# Retro_Programmer-v0_1.net
KiCad netlist of a schematic drawn in EAGLE
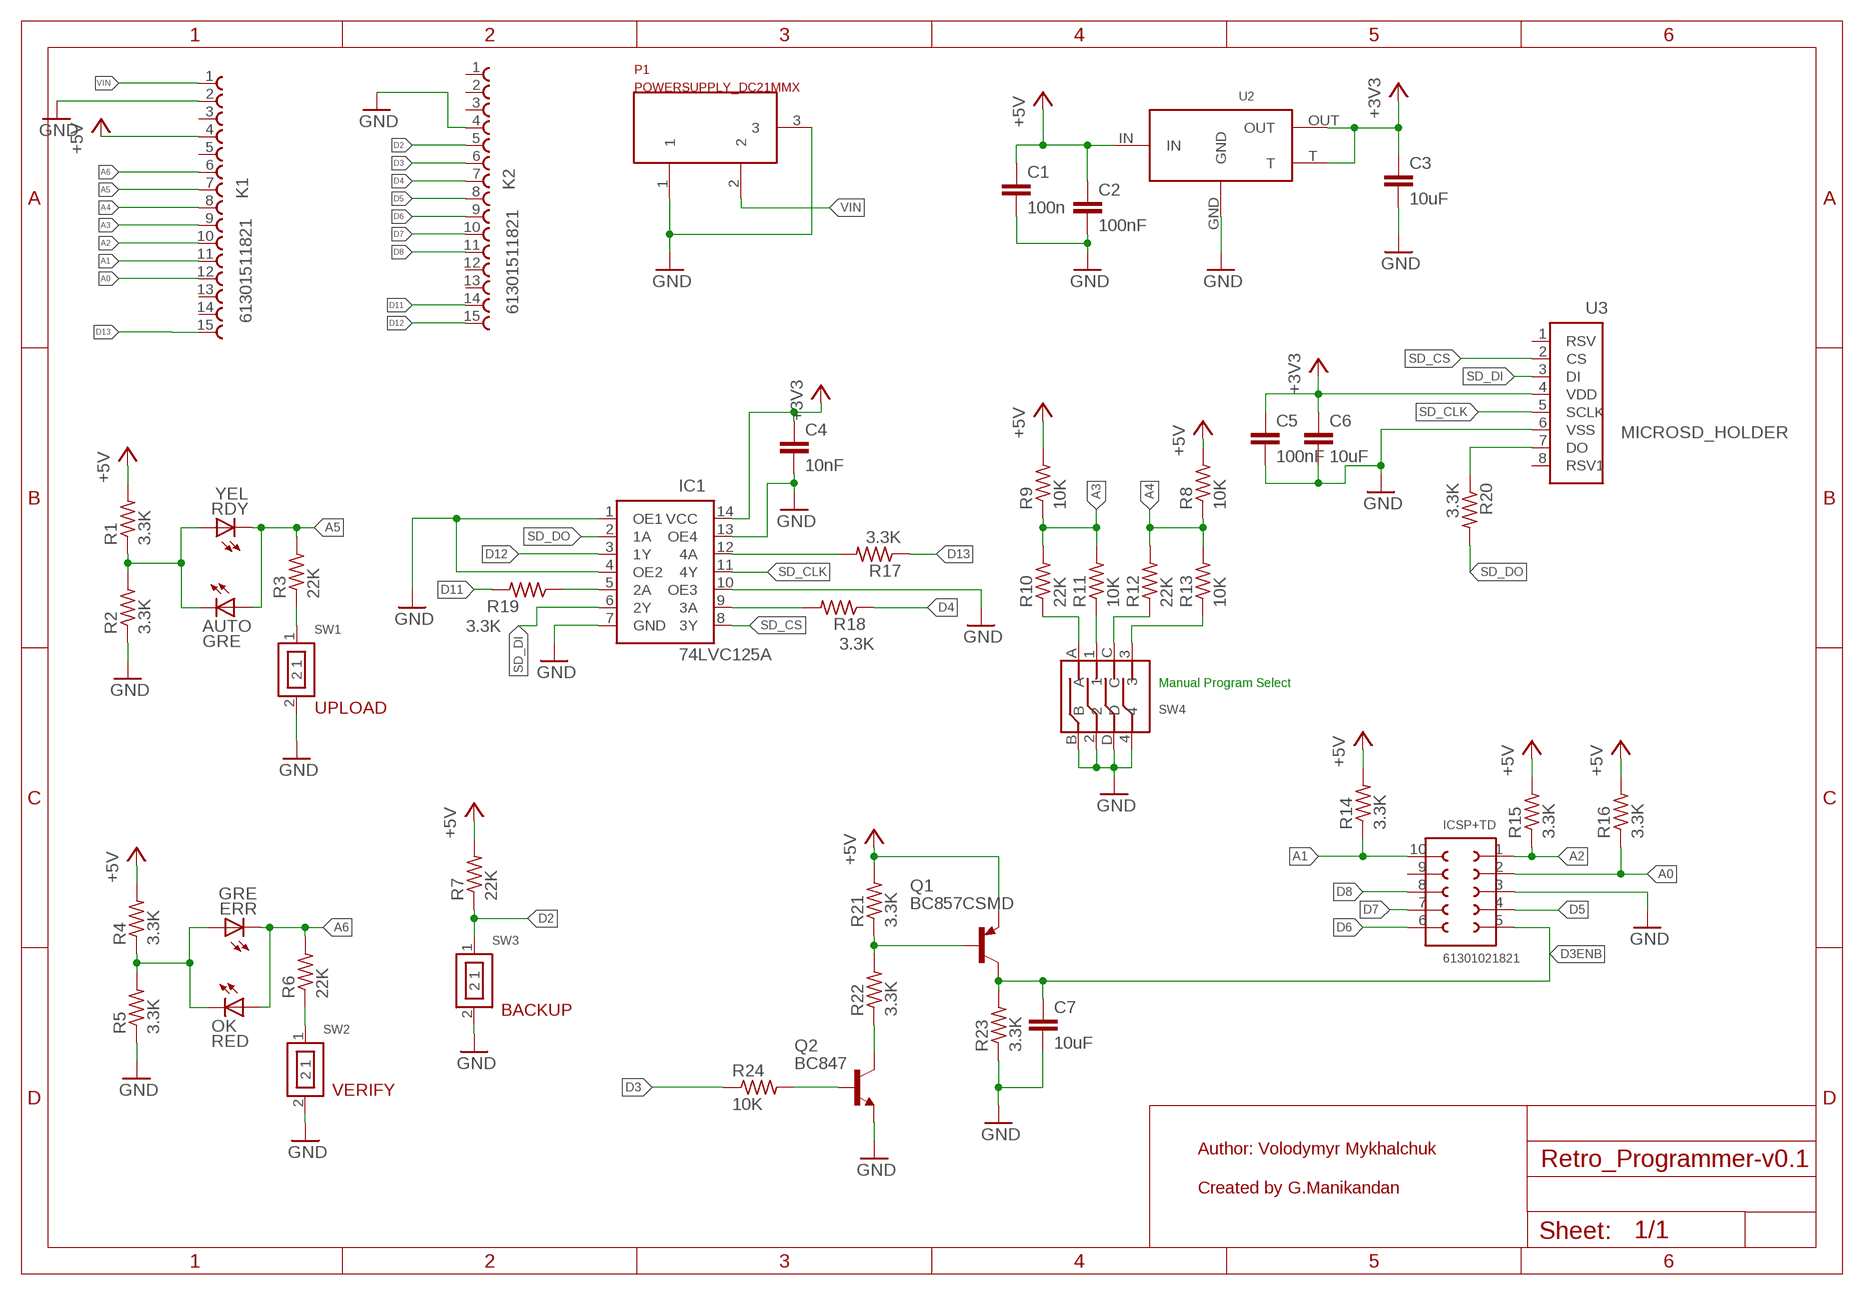
[diagram p0: schematic, sheet 1]

(export (version "E")
  (design (tool "Eeschema 10.0.6"))
  (components
    (comp (ref "AUTO")
      (value "GRE")
      (footprint "eagle-import:CHIPLED_1206")
      (libsource (lib "eagle-import") (part "LEDCHIPLED_1206"))
    )
    (comp (ref "C1")
      (value "100n")
      (footprint "eagle-import:C1206")
      (libsource (lib "eagle-import") (part "C-EUC1206"))
    )
    (comp (ref "C2")
      (value "100nF")
      (footprint "eagle-import:C1206")
      (libsource (lib "eagle-import") (part "C-EUC1206"))
    )
    (comp (ref "C3")
      (value "10uF")
      (footprint "eagle-import:C1206")
      (libsource (lib "eagle-import") (part "C-EUC1206"))
    )
    (comp (ref "C4")
      (value "10nF")
      (footprint "eagle-import:C1206")
      (libsource (lib "eagle-import") (part "C-EUC1206"))
    )
    (comp (ref "C5")
      (value "100nF")
      (footprint "eagle-import:C1206")
      (libsource (lib "eagle-import") (part "C-EUC1206"))
    )
    (comp (ref "C6")
      (value "10uF")
      (footprint "eagle-import:C1206")
      (libsource (lib "eagle-import") (part "C-EUC1206"))
    )
    (comp (ref "C7")
      (value "10uF")
      (footprint "eagle-import:C1206")
      (libsource (lib "eagle-import") (part "C-EUC1206"))
    )
    (comp (ref "ERR")
      (value "GRE")
      (footprint "eagle-import:CHIPLED_1206")
      (libsource (lib "eagle-import") (part "LEDCHIPLED_1206"))
    )
    (comp (ref "IC1")
      (value "74LVC125A")
      (footprint "eagle-import:SOIC14_74L")
      (libsource (lib "eagle-import") (part "74LVC125A"))
    )
    (comp (ref "ICSP+TD")
      (value "61301021821")
      (footprint "eagle-import:61301021821")
      (libsource (lib "eagle-import") (part "61301021821"))
    )
    (comp (ref "K1")
      (value "61301511821")
      (footprint "eagle-import:61301511821")
      (libsource (lib "eagle-import") (part "61301511821"))
    )
    (comp (ref "K2")
      (value "61301511821")
      (footprint "eagle-import:61301511821")
      (libsource (lib "eagle-import") (part "61301511821"))
    )
    (comp (ref "OK")
      (value "RED")
      (footprint "eagle-import:CHIPLED_1206")
      (libsource (lib "eagle-import") (part "LEDCHIPLED_1206"))
    )
    (comp (ref "P1")
      (value "POWERSUPPLY_DC21MMX")
      (footprint "eagle-import:POWERSUPPLY_DC-21MM")
      (libsource (lib "eagle-import") (part "POWERSUPPLY_DC21MMX"))
    )
    (comp (ref "Q1")
      (value "BC857CSMD")
      (footprint "eagle-import:SOT23-BEC")
      (libsource (lib "eagle-import") (part "BC857SMDC"))
    )
    (comp (ref "Q2")
      (value "BC847")
      (footprint "eagle-import:SOT23")
      (libsource (lib "eagle-import") (part "BC847"))
    )
    (comp (ref "R1")
      (value "3.3K")
      (footprint "eagle-import:R1206")
      (libsource (lib "eagle-import") (part "R-US_R1206"))
    )
    (comp (ref "R2")
      (value "3.3K")
      (footprint "eagle-import:R1206")
      (libsource (lib "eagle-import") (part "R-US_R1206"))
    )
    (comp (ref "R3")
      (value "22K")
      (footprint "eagle-import:R1206")
      (libsource (lib "eagle-import") (part "R-US_R1206"))
    )
    (comp (ref "R4")
      (value "3.3K")
      (footprint "eagle-import:R1206")
      (libsource (lib "eagle-import") (part "R-US_R1206"))
    )
    (comp (ref "R5")
      (value "3.3K")
      (footprint "eagle-import:R1206")
      (libsource (lib "eagle-import") (part "R-US_R1206"))
    )
    (comp (ref "R6")
      (value "22K")
      (footprint "eagle-import:R1206")
      (libsource (lib "eagle-import") (part "R-US_R1206"))
    )
    (comp (ref "R7")
      (value "22K")
      (footprint "eagle-import:R1206")
      (libsource (lib "eagle-import") (part "R-US_R1206"))
    )
    (comp (ref "R8")
      (value "10K")
      (footprint "eagle-import:R1206")
      (libsource (lib "eagle-import") (part "R-US_R1206"))
    )
    (comp (ref "R9")
      (value "10K")
      (footprint "eagle-import:R1206")
      (libsource (lib "eagle-import") (part "R-US_R1206"))
    )
    (comp (ref "R10")
      (value "22K")
      (footprint "eagle-import:R1206")
      (libsource (lib "eagle-import") (part "R-US_R1206"))
    )
    (comp (ref "R11")
      (value "10K")
      (footprint "eagle-import:R1206")
      (libsource (lib "eagle-import") (part "R-US_R1206"))
    )
    (comp (ref "R12")
      (value "22K")
      (footprint "eagle-import:R1206")
      (libsource (lib "eagle-import") (part "R-US_R1206"))
    )
    (comp (ref "R13")
      (value "10K")
      (footprint "eagle-import:R1206")
      (libsource (lib "eagle-import") (part "R-US_R1206"))
    )
    (comp (ref "R14")
      (value "3.3K")
      (footprint "eagle-import:R1206")
      (libsource (lib "eagle-import") (part "R-US_R1206"))
    )
    (comp (ref "R15")
      (value "3.3K")
      (footprint "eagle-import:R1206")
      (libsource (lib "eagle-import") (part "R-US_R1206"))
    )
    (comp (ref "R16")
      (value "3.3K")
      (footprint "eagle-import:R1206")
      (libsource (lib "eagle-import") (part "R-US_R1206"))
    )
    (comp (ref "R17")
      (value "3.3K")
      (footprint "eagle-import:R1206")
      (libsource (lib "eagle-import") (part "R-US_R1206"))
    )
    (comp (ref "R18")
      (value "3.3K")
      (footprint "eagle-import:R1206")
      (libsource (lib "eagle-import") (part "R-US_R1206"))
    )
    (comp (ref "R19")
      (value "3.3K")
      (footprint "eagle-import:R1206")
      (libsource (lib "eagle-import") (part "R-US_R1206"))
    )
    (comp (ref "R20")
      (value "3.3K")
      (footprint "eagle-import:R1206")
      (libsource (lib "eagle-import") (part "R-US_R1206"))
    )
    (comp (ref "R21")
      (value "3.3K")
      (footprint "eagle-import:R1206")
      (libsource (lib "eagle-import") (part "R-US_R1206"))
    )
    (comp (ref "R22")
      (value "3.3K")
      (footprint "eagle-import:R1206")
      (libsource (lib "eagle-import") (part "R-US_R1206"))
    )
    (comp (ref "R23")
      (value "3.3K")
      (footprint "eagle-import:R1206")
      (libsource (lib "eagle-import") (part "R-US_R1206"))
    )
    (comp (ref "R24")
      (value "10K")
      (footprint "eagle-import:R1206")
      (libsource (lib "eagle-import") (part "R-US_R1206"))
    )
    (comp (ref "RDY")
      (value "YEL")
      (footprint "eagle-import:CHIPLED_1206")
      (libsource (lib "eagle-import") (part "LEDCHIPLED_1206"))
    )
    (comp (ref "SW1")
      (value "SPUSH")
      (footprint "eagle-import:SLIDE1")
      (libsource (lib "eagle-import") (part "SPUSH"))
    )
    (comp (ref "SW2")
      (value "SPUSH")
      (footprint "eagle-import:SLIDE1")
      (libsource (lib "eagle-import") (part "SPUSH"))
    )
    (comp (ref "SW3")
      (value "SPUSH")
      (footprint "eagle-import:SLIDE1")
      (libsource (lib "eagle-import") (part "SPUSH"))
    )
    (comp (ref "SW4")
      (value "SLIDE_WAY4")
      (footprint "eagle-import:SLIDESWITCH_4")
      (libsource (lib "eagle-import") (part "SLIDE_WAY4"))
    )
    (comp (ref "U2")
      (value "LT1117")
      (footprint "eagle-import:SOT223")
      (libsource (lib "eagle-import") (part "LT1117"))
    )
    (comp (ref "U3")
      (value "MICROSD_HOLDER")
      (footprint "eagle-import:SDCARD_HOLDER")
      (libsource (lib "eagle-import") (part "MICROSD_HOLDER"))
    )
  )
  (nets
    (net (code "1") (name "+3V3") (class "Default")
      (node (ref "C3") (pin "1") (pinfunction "1_1") (pintype "passive"))
      (node (ref "C4") (pin "1") (pinfunction "1_1") (pintype "passive"))
      (node (ref "C5") (pin "1") (pinfunction "1_1") (pintype "passive"))
      (node (ref "C6") (pin "1") (pinfunction "1_1") (pintype "passive"))
      (node (ref "IC1") (pin "14") (pinfunction "VCC_14") (pintype "bidirectional"))
      (node (ref "U2") (pin "OUT") (pinfunction "OUT_OUT") (pintype "bidirectional"))
      (node (ref "U2") (pin "T") (pinfunction "T_T") (pintype "bidirectional"))
      (node (ref "U3") (pin "4") (pinfunction "VDD_4") (pintype "bidirectional"))
    )
    (net (code "2") (name "+5V") (class "Default")
      (node (ref "C1") (pin "1") (pinfunction "1_1") (pintype "passive"))
      (node (ref "C2") (pin "1") (pinfunction "1_1") (pintype "passive"))
      (node (ref "K1") (pin "4") (pinfunction "4_4") (pintype "passive"))
      (node (ref "Q1") (pin "E") (pinfunction "E_E") (pintype "passive"))
      (node (ref "R1") (pin "2") (pinfunction "2_2") (pintype "passive"))
      (node (ref "R14") (pin "2") (pinfunction "2_2") (pintype "passive"))
      (node (ref "R15") (pin "2") (pinfunction "2_2") (pintype "passive"))
      (node (ref "R16") (pin "2") (pinfunction "2_2") (pintype "passive"))
      (node (ref "R21") (pin "2") (pinfunction "2_2") (pintype "passive"))
      (node (ref "R4") (pin "2") (pinfunction "2_2") (pintype "passive"))
      (node (ref "R7") (pin "2") (pinfunction "2_2") (pintype "passive"))
      (node (ref "R8") (pin "2") (pinfunction "2_2") (pintype "passive"))
      (node (ref "R9") (pin "2") (pinfunction "2_2") (pintype "passive"))
      (node (ref "U2") (pin "IN") (pinfunction "IN_IN") (pintype "bidirectional"))
    )
    (net (code "3") (name "A0") (class "Default")
      (node (ref "ICSP+TD") (pin "2") (pinfunction "2_2") (pintype "passive"))
      (node (ref "K1") (pin "12") (pinfunction "12_12") (pintype "passive"))
      (node (ref "R16") (pin "1") (pinfunction "1_1") (pintype "passive"))
    )
    (net (code "4") (name "A1") (class "Default")
      (node (ref "ICSP+TD") (pin "10") (pinfunction "10_10") (pintype "passive"))
      (node (ref "K1") (pin "11") (pinfunction "11_11") (pintype "passive"))
      (node (ref "R14") (pin "1") (pinfunction "1_1") (pintype "passive"))
    )
    (net (code "5") (name "A2") (class "Default")
      (node (ref "ICSP+TD") (pin "1") (pinfunction "1_1") (pintype "passive"))
      (node (ref "K1") (pin "10") (pinfunction "10_10") (pintype "passive"))
      (node (ref "R15") (pin "1") (pinfunction "1_1") (pintype "passive"))
    )
    (net (code "6") (name "A3") (class "Default")
      (node (ref "K1") (pin "9") (pinfunction "9_9") (pintype "passive"))
      (node (ref "R10") (pin "2") (pinfunction "2_2") (pintype "passive"))
      (node (ref "R11") (pin "2") (pinfunction "2_2") (pintype "passive"))
      (node (ref "R9") (pin "1") (pinfunction "1_1") (pintype "passive"))
    )
    (net (code "7") (name "A4") (class "Default")
      (node (ref "K1") (pin "8") (pinfunction "8_8") (pintype "passive"))
      (node (ref "R12") (pin "2") (pinfunction "2_2") (pintype "passive"))
      (node (ref "R13") (pin "2") (pinfunction "2_2") (pintype "passive"))
      (node (ref "R8") (pin "1") (pinfunction "1_1") (pintype "passive"))
    )
    (net (code "8") (name "A5") (class "Default")
      (node (ref "AUTO") (pin "A") (pinfunction "A_A") (pintype "passive"))
      (node (ref "K1") (pin "7") (pinfunction "7_7") (pintype "passive"))
      (node (ref "R3") (pin "2") (pinfunction "2_2") (pintype "passive"))
      (node (ref "RDY") (pin "C") (pinfunction "C_C") (pintype "passive"))
    )
    (net (code "9") (name "A6") (class "Default")
      (node (ref "ERR") (pin "C") (pinfunction "C_C") (pintype "passive"))
      (node (ref "K1") (pin "6") (pinfunction "6_6") (pintype "passive"))
      (node (ref "OK") (pin "A") (pinfunction "A_A") (pintype "passive"))
      (node (ref "R6") (pin "2") (pinfunction "2_2") (pintype "passive"))
    )
    (net (code "10") (name "D2") (class "Default")
      (node (ref "K2") (pin "5") (pinfunction "5_5") (pintype "passive"))
      (node (ref "R7") (pin "1") (pinfunction "1_1") (pintype "passive"))
      (node (ref "SW3") (pin "1") (pinfunction "1_1") (pintype "bidirectional"))
    )
    (net (code "11") (name "D3") (class "Default")
      (node (ref "K2") (pin "6") (pinfunction "6_6") (pintype "passive"))
      (node (ref "R24") (pin "1") (pinfunction "1_1") (pintype "passive"))
    )
    (net (code "12") (name "D3ENB") (class "Default")
      (node (ref "C7") (pin "1") (pinfunction "1_1") (pintype "passive"))
      (node (ref "ICSP+TD") (pin "5") (pinfunction "5_5") (pintype "passive"))
      (node (ref "Q1") (pin "C") (pinfunction "C_C") (pintype "passive"))
      (node (ref "R23") (pin "2") (pinfunction "2_2") (pintype "passive"))
    )
    (net (code "13") (name "D4") (class "Default")
      (node (ref "K2") (pin "7") (pinfunction "7_7") (pintype "passive"))
      (node (ref "R18") (pin "1") (pinfunction "1_1") (pintype "passive"))
    )
    (net (code "14") (name "D5") (class "Default")
      (node (ref "ICSP+TD") (pin "4") (pinfunction "4_4") (pintype "passive"))
      (node (ref "K2") (pin "8") (pinfunction "8_8") (pintype "passive"))
    )
    (net (code "15") (name "D6") (class "Default")
      (node (ref "ICSP+TD") (pin "6") (pinfunction "6_6") (pintype "passive"))
      (node (ref "K2") (pin "9") (pinfunction "9_9") (pintype "passive"))
    )
    (net (code "16") (name "D7") (class "Default")
      (node (ref "ICSP+TD") (pin "7") (pinfunction "7_7") (pintype "passive"))
      (node (ref "K2") (pin "10") (pinfunction "10_10") (pintype "passive"))
    )
    (net (code "17") (name "D8") (class "Default")
      (node (ref "ICSP+TD") (pin "8") (pinfunction "8_8") (pintype "passive"))
      (node (ref "K2") (pin "11") (pinfunction "11_11") (pintype "passive"))
    )
    (net (code "18") (name "D11") (class "Default")
      (node (ref "K2") (pin "14") (pinfunction "14_14") (pintype "passive"))
      (node (ref "R19") (pin "2") (pinfunction "2_2") (pintype "passive"))
    )
    (net (code "19") (name "D12") (class "Default")
      (node (ref "IC1") (pin "3") (pinfunction "1Y_3") (pintype "bidirectional"))
      (node (ref "K2") (pin "15") (pinfunction "15_15") (pintype "passive"))
    )
    (net (code "20") (name "D13") (class "Default")
      (node (ref "K1") (pin "15") (pinfunction "15_15") (pintype "passive"))
      (node (ref "R17") (pin "1") (pinfunction "1_1") (pintype "passive"))
    )
    (net (code "21") (name "GND") (class "Default")
      (node (ref "C1") (pin "2") (pinfunction "2_2") (pintype "passive"))
      (node (ref "C2") (pin "2") (pinfunction "2_2") (pintype "passive"))
      (node (ref "C3") (pin "2") (pinfunction "2_2") (pintype "passive"))
      (node (ref "C4") (pin "2") (pinfunction "2_2") (pintype "passive"))
      (node (ref "C5") (pin "2") (pinfunction "2_2") (pintype "passive"))
      (node (ref "C6") (pin "2") (pinfunction "2_2") (pintype "passive"))
      (node (ref "C7") (pin "2") (pinfunction "2_2") (pintype "passive"))
      (node (ref "IC1") (pin "1") (pinfunction "OE1_1") (pintype "bidirectional"))
      (node (ref "IC1") (pin "10") (pinfunction "OE3_10") (pintype "bidirectional"))
      (node (ref "IC1") (pin "13") (pinfunction "OE4_13") (pintype "bidirectional"))
      (node (ref "IC1") (pin "4") (pinfunction "OE2_4") (pintype "bidirectional"))
      (node (ref "IC1") (pin "7") (pinfunction "GND_7") (pintype "bidirectional"))
      (node (ref "ICSP+TD") (pin "3") (pinfunction "3_3") (pintype "passive"))
      (node (ref "K1") (pin "2") (pinfunction "2_2") (pintype "passive"))
      (node (ref "K2") (pin "4") (pinfunction "4_4") (pintype "passive"))
      (node (ref "P1") (pin "1") (pinfunction "1_1") (pintype "power_in"))
      (node (ref "P1") (pin "3") (pinfunction "3_3") (pintype "power_in"))
      (node (ref "Q2") (pin "2") (pinfunction "E_2") (pintype "passive"))
      (node (ref "R2") (pin "1") (pinfunction "1_1") (pintype "passive"))
      (node (ref "R23") (pin "1") (pinfunction "1_1") (pintype "passive"))
      (node (ref "R5") (pin "1") (pinfunction "1_1") (pintype "passive"))
      (node (ref "SW1") (pin "2") (pinfunction "2_2") (pintype "bidirectional"))
      (node (ref "SW2") (pin "2") (pinfunction "2_2") (pintype "bidirectional"))
      (node (ref "SW3") (pin "2") (pinfunction "2_2") (pintype "bidirectional"))
      (node (ref "SW4") (pin "2") (pinfunction "2_2") (pintype "bidirectional"))
      (node (ref "SW4") (pin "4") (pinfunction "4_4") (pintype "bidirectional"))
      (node (ref "SW4") (pin "B") (pinfunction "B_B") (pintype "bidirectional"))
      (node (ref "SW4") (pin "D") (pinfunction "D_D") (pintype "bidirectional"))
      (node (ref "U2") (pin "GND") (pinfunction "GND_GND") (pintype "bidirectional"))
      (node (ref "U3") (pin "6") (pinfunction "VSS_6") (pintype "bidirectional"))
    )
    (net (code "22") (name "Net-(AUTO-PadC)") (class "Default")
      (node (ref "AUTO") (pin "C") (pinfunction "C_C") (pintype "passive"))
      (node (ref "R1") (pin "1") (pinfunction "1_1") (pintype "passive"))
      (node (ref "R2") (pin "2") (pinfunction "2_2") (pintype "passive"))
      (node (ref "RDY") (pin "A") (pinfunction "A_A") (pintype "passive"))
    )
    (net (code "23") (name "Net-(ERR-PadA)") (class "Default")
      (node (ref "ERR") (pin "A") (pinfunction "A_A") (pintype "passive"))
      (node (ref "OK") (pin "C") (pinfunction "C_C") (pintype "passive"))
      (node (ref "R4") (pin "1") (pinfunction "1_1") (pintype "passive"))
      (node (ref "R5") (pin "2") (pinfunction "2_2") (pintype "passive"))
    )
    (net (code "24") (name "Net-(IC1-2A)") (class "Default")
      (node (ref "IC1") (pin "5") (pinfunction "2A_5") (pintype "bidirectional"))
      (node (ref "R19") (pin "1") (pinfunction "1_1") (pintype "passive"))
    )
    (net (code "25") (name "Net-(IC1-3A)") (class "Default")
      (node (ref "IC1") (pin "9") (pinfunction "3A_9") (pintype "bidirectional"))
      (node (ref "R18") (pin "2") (pinfunction "2_2") (pintype "passive"))
    )
    (net (code "26") (name "Net-(IC1-4A)") (class "Default")
      (node (ref "IC1") (pin "12") (pinfunction "4A_12") (pintype "bidirectional"))
      (node (ref "R17") (pin "2") (pinfunction "2_2") (pintype "passive"))
    )
    (net (code "27") (name "Net-(Q1-PadB)") (class "Default")
      (node (ref "Q1") (pin "B") (pinfunction "B_B") (pintype "passive"))
      (node (ref "R21") (pin "1") (pinfunction "1_1") (pintype "passive"))
      (node (ref "R22") (pin "2") (pinfunction "2_2") (pintype "passive"))
    )
    (net (code "28") (name "Net-(Q2-B)") (class "Default")
      (node (ref "Q2") (pin "1") (pinfunction "B_1") (pintype "passive"))
      (node (ref "R24") (pin "2") (pinfunction "2_2") (pintype "passive"))
    )
    (net (code "29") (name "Net-(Q2-C)") (class "Default")
      (node (ref "Q2") (pin "3") (pinfunction "C_3") (pintype "passive"))
      (node (ref "R22") (pin "1") (pinfunction "1_1") (pintype "passive"))
    )
    (net (code "30") (name "Net-(R3-Pad1)") (class "Default")
      (node (ref "R3") (pin "1") (pinfunction "1_1") (pintype "passive"))
      (node (ref "SW1") (pin "1") (pinfunction "1_1") (pintype "bidirectional"))
    )
    (net (code "31") (name "Net-(R6-Pad1)") (class "Default")
      (node (ref "R6") (pin "1") (pinfunction "1_1") (pintype "passive"))
      (node (ref "SW2") (pin "1") (pinfunction "1_1") (pintype "bidirectional"))
    )
    (net (code "32") (name "Net-(R10-Pad1)") (class "Default")
      (node (ref "R10") (pin "1") (pinfunction "1_1") (pintype "passive"))
      (node (ref "SW4") (pin "A") (pinfunction "A_A") (pintype "bidirectional"))
    )
    (net (code "33") (name "Net-(R11-Pad1)") (class "Default")
      (node (ref "R11") (pin "1") (pinfunction "1_1") (pintype "passive"))
      (node (ref "SW4") (pin "1") (pinfunction "1_1") (pintype "bidirectional"))
    )
    (net (code "34") (name "Net-(R12-Pad1)") (class "Default")
      (node (ref "R12") (pin "1") (pinfunction "1_1") (pintype "passive"))
      (node (ref "SW4") (pin "C") (pinfunction "C_C") (pintype "bidirectional"))
    )
    (net (code "35") (name "Net-(R13-Pad1)") (class "Default")
      (node (ref "R13") (pin "1") (pinfunction "1_1") (pintype "passive"))
      (node (ref "SW4") (pin "3") (pinfunction "3_3") (pintype "bidirectional"))
    )
    (net (code "36") (name "Net-(U3-DO)") (class "Default")
      (node (ref "R20") (pin "1") (pinfunction "1_1") (pintype "passive"))
      (node (ref "U3") (pin "7") (pinfunction "DO_7") (pintype "bidirectional"))
    )
    (net (code "37") (name "SD_CLK") (class "Default")
      (node (ref "IC1") (pin "11") (pinfunction "4Y_11") (pintype "bidirectional"))
      (node (ref "U3") (pin "5") (pinfunction "SCLK_5") (pintype "bidirectional"))
    )
    (net (code "38") (name "SD_CS") (class "Default")
      (node (ref "IC1") (pin "8") (pinfunction "3Y_8") (pintype "bidirectional"))
      (node (ref "U3") (pin "2") (pinfunction "CS_2") (pintype "bidirectional"))
    )
    (net (code "39") (name "SD_DI") (class "Default")
      (node (ref "IC1") (pin "6") (pinfunction "2Y_6") (pintype "bidirectional"))
      (node (ref "U3") (pin "3") (pinfunction "DI_3") (pintype "bidirectional"))
    )
    (net (code "40") (name "SD_DO") (class "Default")
      (node (ref "IC1") (pin "2") (pinfunction "1A_2") (pintype "bidirectional"))
      (node (ref "R20") (pin "2") (pinfunction "2_2") (pintype "passive"))
    )
    (net (code "41") (name "VIN") (class "Default")
      (node (ref "K1") (pin "1") (pinfunction "1_1") (pintype "passive"))
      (node (ref "P1") (pin "2") (pinfunction "2_2") (pintype "power_in"))
    )
    (net (code "42") (name "unconnected-(ICSP+TD-Pad9)") (class "Default")
      (node (ref "ICSP+TD") (pin "9") (pinfunction "9_9") (pintype "passive"))
    )
    (net (code "43") (name "unconnected-(K1-Pad3)") (class "Default")
      (node (ref "K1") (pin "3") (pinfunction "3_3") (pintype "passive"))
    )
    (net (code "44") (name "unconnected-(K1-Pad5)") (class "Default")
      (node (ref "K1") (pin "5") (pinfunction "5_5") (pintype "passive"))
    )
    (net (code "45") (name "unconnected-(K1-Pad13)") (class "Default")
      (node (ref "K1") (pin "13") (pinfunction "13_13") (pintype "passive"))
    )
    (net (code "46") (name "unconnected-(K1-Pad14)") (class "Default")
      (node (ref "K1") (pin "14") (pinfunction "14_14") (pintype "passive"))
    )
    (net (code "47") (name "unconnected-(K2-Pad1)") (class "Default")
      (node (ref "K2") (pin "1") (pinfunction "1_1") (pintype "passive"))
    )
    (net (code "48") (name "unconnected-(K2-Pad2)") (class "Default")
      (node (ref "K2") (pin "2") (pinfunction "2_2") (pintype "passive"))
    )
    (net (code "49") (name "unconnected-(K2-Pad3)") (class "Default")
      (node (ref "K2") (pin "3") (pinfunction "3_3") (pintype "passive"))
    )
    (net (code "50") (name "unconnected-(K2-Pad12)") (class "Default")
      (node (ref "K2") (pin "12") (pinfunction "12_12") (pintype "passive"))
    )
    (net (code "51") (name "unconnected-(K2-Pad13)") (class "Default")
      (node (ref "K2") (pin "13") (pinfunction "13_13") (pintype "passive"))
    )
    (net (code "52") (name "unconnected-(U3-RSV-Pad1)") (class "Default")
      (node (ref "U3") (pin "1") (pinfunction "RSV_1") (pintype "bidirectional"))
    )
    (net (code "53") (name "unconnected-(U3-RSV1-Pad8)") (class "Default")
      (node (ref "U3") (pin "8") (pinfunction "RSV1_8") (pintype "bidirectional"))
    )
  )
)
